# term_work.net
KiCad netlist of a schematic drawn in EasyEDA Pro
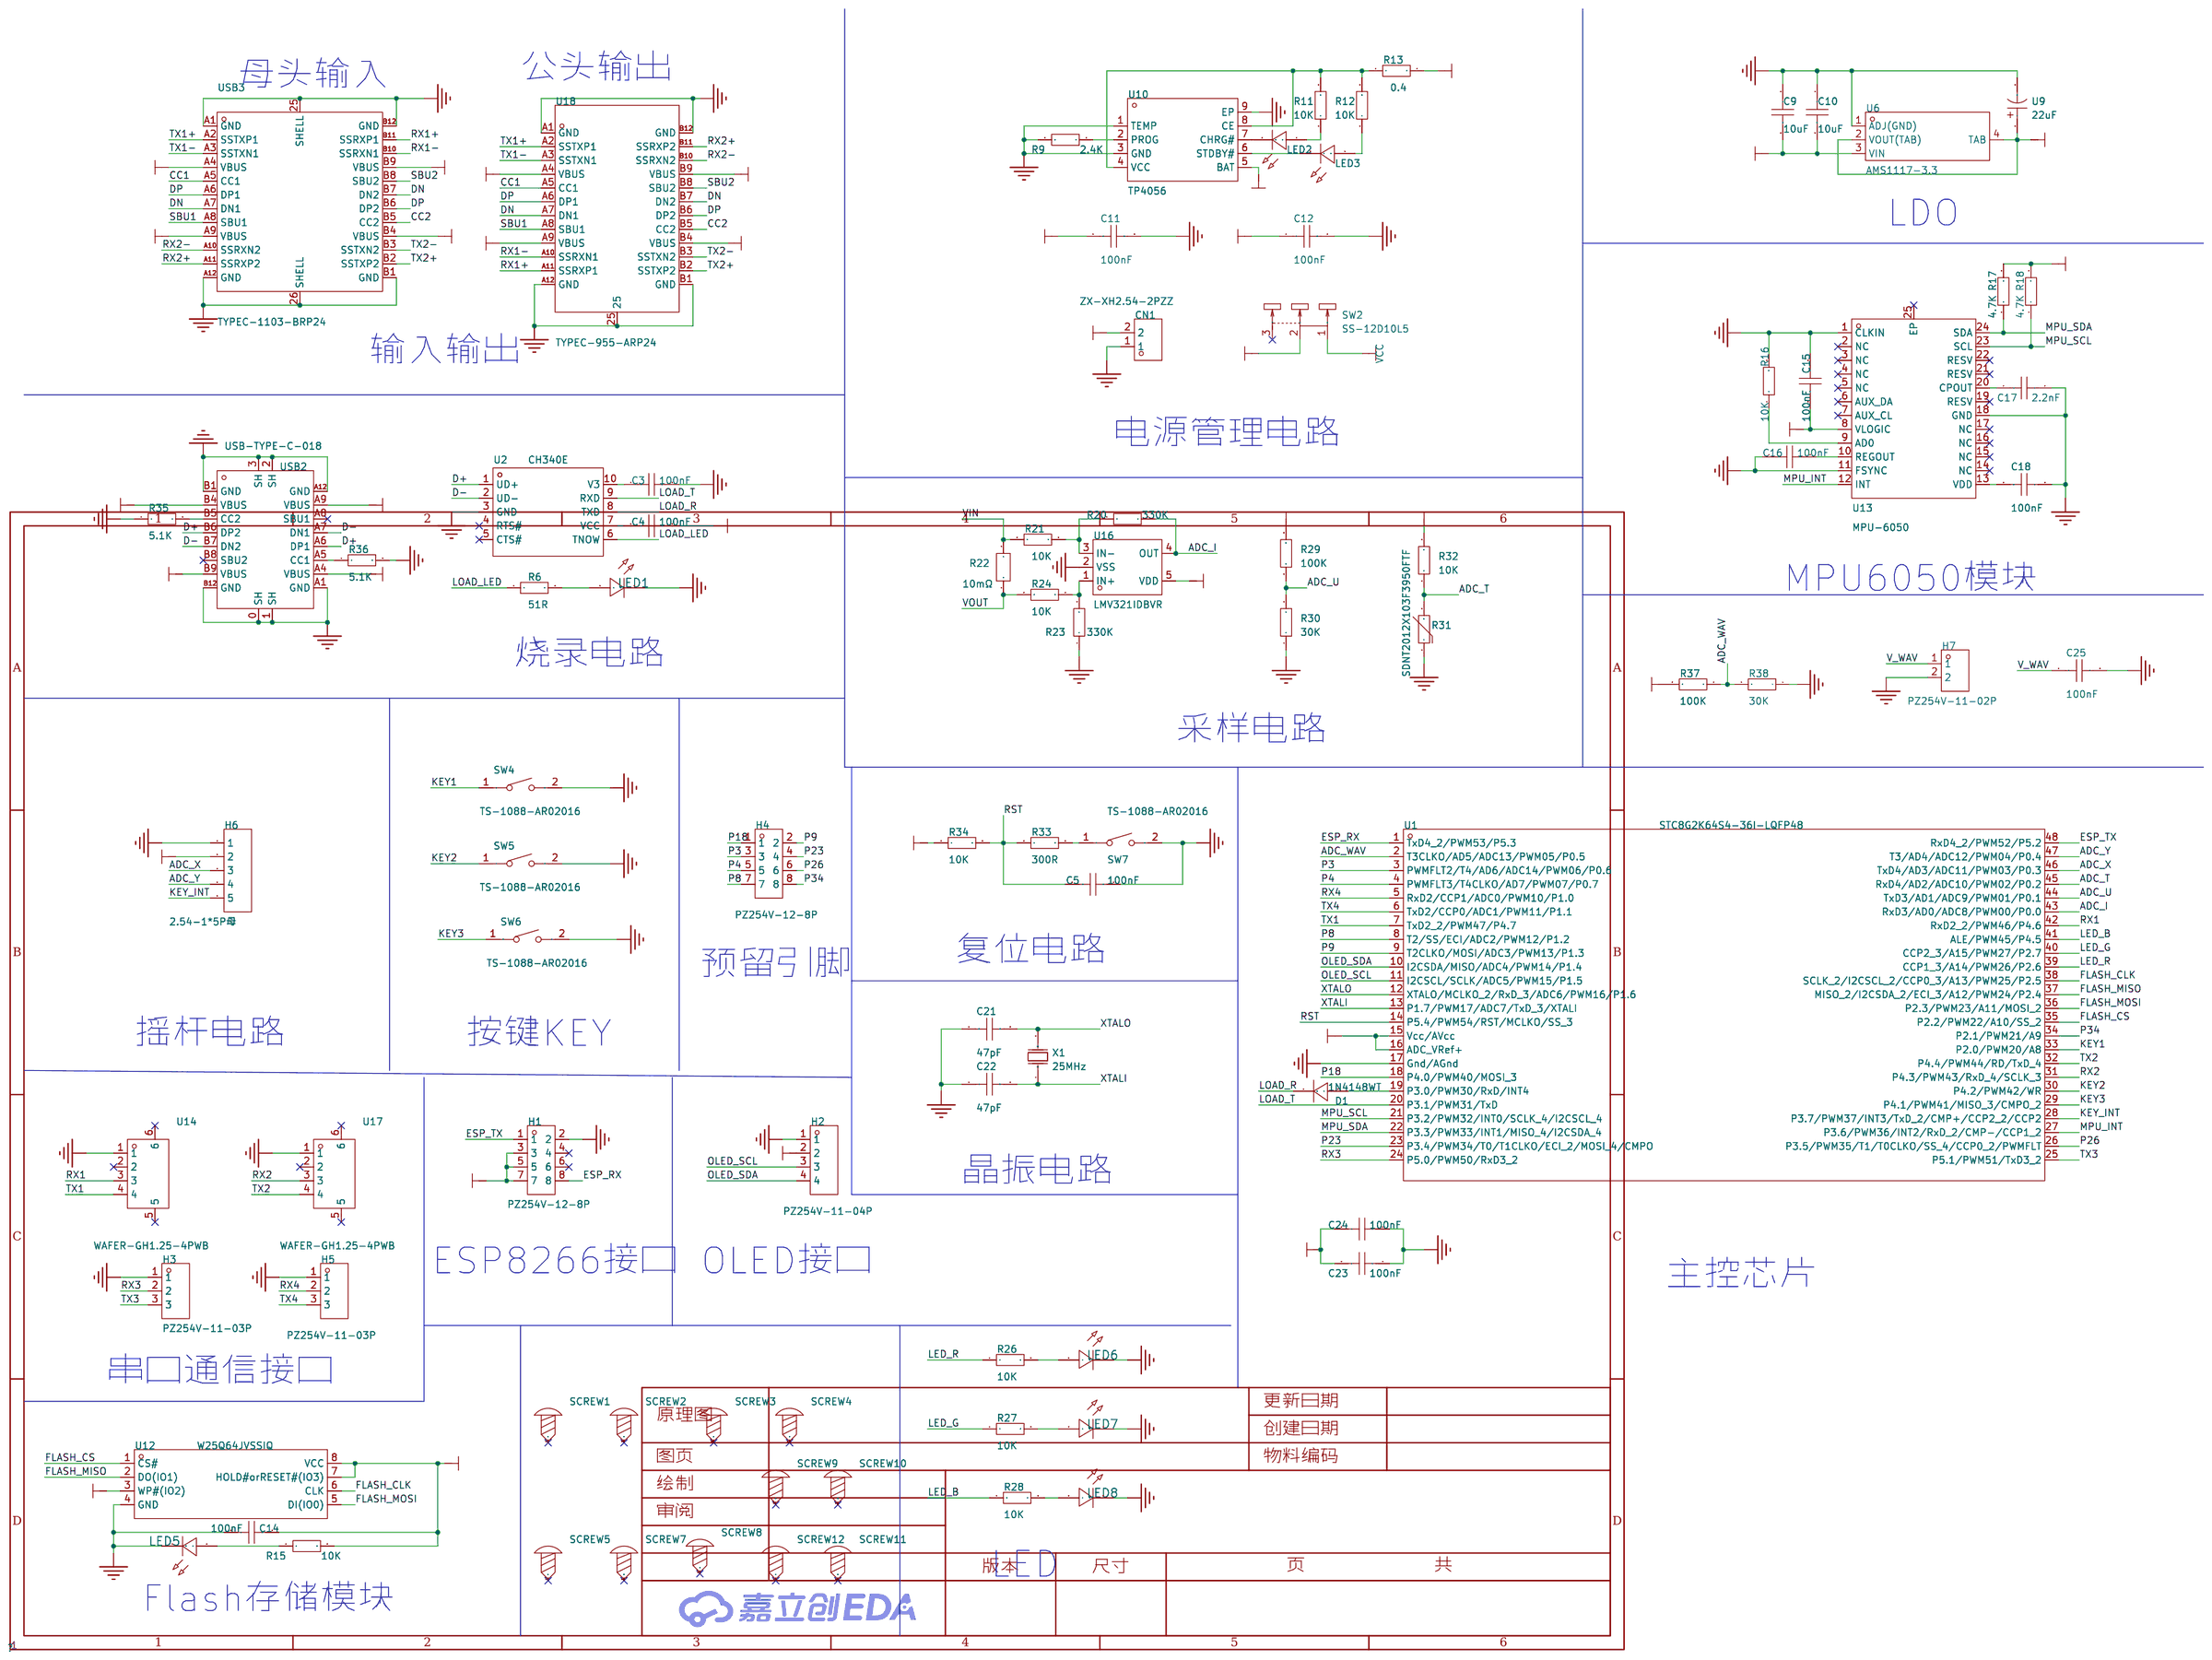
[diagram p0: schematic sheet]

(export (version "E")
  (design (tool "Eeschema 10.0.6"))
  (components
    (comp (ref "C3")
      (value "100nF")
      (footprint "easyedapro:C0603")
      (libsource (lib "easyedapro") (part "CapAcitance"))
    )
    (comp (ref "C4")
      (value "100nF")
      (footprint "easyedapro:C0603")
      (libsource (lib "easyedapro") (part "CapAcitance"))
    )
    (comp (ref "C5")
      (value "100nF")
      (footprint "easyedapro:C0603")
      (libsource (lib "easyedapro") (part "CapAcitance"))
    )
    (comp (ref "C9")
      (value "10uF")
      (footprint "easyedapro:C0603")
      (libsource (lib "easyedapro") (part "CapAcitance"))
    )
    (comp (ref "C10")
      (value "10uF")
      (footprint "easyedapro:C0603")
      (libsource (lib "easyedapro") (part "CapAcitance"))
    )
    (comp (ref "C11")
      (value "100nF")
      (footprint "easyedapro:C0603")
      (libsource (lib "easyedapro") (part "CapAcitance"))
    )
    (comp (ref "C12")
      (value "100nF")
      (footprint "easyedapro:C0603")
      (libsource (lib "easyedapro") (part "CapAcitance"))
    )
    (comp (ref "C14")
      (value "100nF")
      (footprint "easyedapro:C0603")
      (libsource (lib "easyedapro") (part "CapAcitance"))
    )
    (comp (ref "C15")
      (value "100nF")
      (footprint "easyedapro:C0603")
      (libsource (lib "easyedapro") (part "CapAcitance"))
    )
    (comp (ref "C16")
      (value "100nF")
      (footprint "easyedapro:C0603")
      (libsource (lib "easyedapro") (part "CapAcitance"))
    )
    (comp (ref "C17")
      (value "2.2nF")
      (footprint "easyedapro:C0603")
      (libsource (lib "easyedapro") (part "CapAcitance"))
    )
    (comp (ref "C18")
      (value "100nF")
      (footprint "easyedapro:C0603")
      (libsource (lib "easyedapro") (part "CapAcitance"))
    )
    (comp (ref "C21")
      (value "47pF")
      (footprint "easyedapro:C0603")
      (libsource (lib "easyedapro") (part "CapAcitance"))
    )
    (comp (ref "C22")
      (value "47pF")
      (footprint "easyedapro:C0603")
      (libsource (lib "easyedapro") (part "CapAcitance"))
    )
    (comp (ref "C23")
      (value "100nF")
      (footprint "easyedapro:C0603")
      (libsource (lib "easyedapro") (part "CapAcitance"))
    )
    (comp (ref "C24")
      (value "100nF")
      (footprint "easyedapro:C0603")
      (libsource (lib "easyedapro") (part "CapAcitance"))
    )
    (comp (ref "C25")
      (value "100nF")
      (footprint "easyedapro:C0603")
      (libsource (lib "easyedapro") (part "CapAcitance"))
    )
    (comp (ref "CN1")
      (value "ZX-XH2.54-2PZZ")
      (footprint "easyedapro:CONN-TH_2P-P2.50_HX25003-2A")
      (fields (field (name "Manufacturer") "Megastar(兆星)"))
      (libsource (lib "easyedapro") (part "ZX-XH2.54-2PZZ"))
    )
    (comp (ref "D1")
      (value "1N4148WT")
      (footprint "easyedapro:SOD-523_L1.2-W0.8-LS1.6-RD")
      (description "二极管配置:独立式;正向压降(Vf):1V@10mA;直流反向耐压(Vr):75V;平均整流电流(Io):300mA;功率:200mW;反向恢复时间(trr):4ns;")
      (fields (field (name "Manufacturer") "onsemi(安森美)"))
      (libsource (lib "easyedapro") (part "1N4148WT_C232841"))
    )
    (comp (ref "H1")
      (value "PZ254V-12-8P")
      (footprint "easyedapro:HDR-TH_8P-P2.54-V-M-R2-C4-S2.54")
      (fields (field (name "Manufacturer") "XFCN(兴飞)"))
      (libsource (lib "easyedapro") (part "PZ254V-12-8P"))
    )
    (comp (ref "H2")
      (value "PZ254V-11-04P")
      (footprint "easyedapro:HDR-TH_4P-P2.54-V-M")
      (fields (field (name "Manufacturer") "XFCN(兴飞)"))
      (libsource (lib "easyedapro") (part "PZ254V-11-04P_C2691448"))
    )
    (comp (ref "H3")
      (value "PZ254V-11-03P")
      (footprint "easyedapro:HDR-TH_3P-P2.54-V-M")
      (fields (field (name "Manufacturer") "XFCN(兴飞)"))
      (libsource (lib "easyedapro") (part "PZ254V-11-03P_C2937625"))
    )
    (comp (ref "H4")
      (value "PZ254V-12-8P")
      (footprint "easyedapro:HDR-TH_8P-P2.54-V-M-R2-C4-S2.54")
      (fields (field (name "Manufacturer") "XFCN(兴飞)"))
      (libsource (lib "easyedapro") (part "PZ254V-12-8P"))
    )
    (comp (ref "H5")
      (value "PZ254V-11-03P")
      (footprint "easyedapro:HDR-TH_3P-P2.54-V-M")
      (fields (field (name "Manufacturer") "XFCN(兴飞)"))
      (libsource (lib "easyedapro") (part "PZ254V-11-03P_C2937625"))
    )
    (comp (ref "H6")
      (value "2.54-1*5P母")
      (footprint "easyedapro:HDR-TH_5P-P2.54-V-F")
      (description "插孔结构:1x5P;间距:2.54mm;行距:-;安装类型:直插;排数:单排;总孔位数:5P;塑高:-;触头材质:-;触头镀层:-;")
      (fields (field (name "Manufacturer") "BOOMELE(博穆精密)"))
      (libsource (lib "easyedapro") (part "Header-Female-2.54_1x5"))
    )
    (comp (ref "H7")
      (value "PZ254V-11-02P")
      (footprint "easyedapro:HDR-TH_2P-P2.54-V-M")
      (fields (field (name "Manufacturer") "XFCN(兴飞)"))
      (libsource (lib "easyedapro") (part "PZ254V-11-02P"))
    )
    (comp (ref "LED1")
      (value "~")
      (footprint "easyedapro:LED_0603")
      (libsource (lib "easyedapro") (part "LED_R"))
    )
    (comp (ref "LED2")
      (value "~")
      (footprint "easyedapro:LED_TH-3mm")
      (libsource (lib "easyedapro") (part "LED_TH-R"))
    )
    (comp (ref "LED3")
      (value "~")
      (footprint "easyedapro:LED_TH-3mm")
      (libsource (lib "easyedapro") (part "LED_TH-R"))
    )
    (comp (ref "LED5")
      (value "~")
      (footprint "easyedapro:LED_0603")
      (libsource (lib "easyedapro") (part "LED_R"))
    )
    (comp (ref "LED6")
      (value "~")
      (footprint "easyedapro:LED_0603")
      (libsource (lib "easyedapro") (part "LED_R"))
    )
    (comp (ref "LED7")
      (value "~")
      (footprint "easyedapro:LED_0603")
      (libsource (lib "easyedapro") (part "LED_R"))
    )
    (comp (ref "LED8")
      (value "~")
      (footprint "easyedapro:LED_0603")
      (libsource (lib "easyedapro") (part "LED_R"))
    )
    (comp (ref "R6") (value "51R") (footprint "easyedapro:R0603") (libsource (lib "easyedapro") (part "电阻")))
    (comp (ref "R9") (value "2.4K") (footprint "easyedapro:R0603") (libsource (lib "easyedapro") (part "电阻")))
    (comp (ref "R11") (value "10K") (footprint "easyedapro:R0603") (libsource (lib "easyedapro") (part "电阻")))
    (comp (ref "R12") (value "10K") (footprint "easyedapro:R0603") (libsource (lib "easyedapro") (part "电阻")))
    (comp (ref "R13") (value "0.4") (footprint "easyedapro:R0603") (libsource (lib "easyedapro") (part "电阻")))
    (comp (ref "R15") (value "10K") (footprint "easyedapro:R0603") (libsource (lib "easyedapro") (part "电阻")))
    (comp (ref "R16") (value "10K") (footprint "easyedapro:R0603") (libsource (lib "easyedapro") (part "电阻")))
    (comp (ref "R17")
      (value "4.7K")
      (footprint "easyedapro:R0603")
      (libsource (lib "easyedapro") (part "电阻"))
    )
    (comp (ref "R18")
      (value "4.7K")
      (footprint "easyedapro:R0603")
      (libsource (lib "easyedapro") (part "电阻"))
    )
    (comp (ref "R20")
      (value "330K")
      (footprint "easyedapro:R0603")
      (libsource (lib "easyedapro") (part "电阻"))
    )
    (comp (ref "R21") (value "10K") (footprint "easyedapro:R0603") (libsource (lib "easyedapro") (part "电阻")))
    (comp (ref "R22")
      (value "10mΩ")
      (footprint "easyedapro:RES-SMD_L6.4-W3.2-1")
      (description "电阻类型:采样电阻;阻值:5mΩ;精度:±1%;功率:3W;安装方式:贴片;")
      (fields
        (field (name "Manufacturer Part") "HoJLR2512-3W-5mR-1%")
        (field (name "Manufacturer") "Milliohm(毫欧)")
      )
      (libsource (lib "easyedapro") (part "HOJLR2512-3W-5MR-1%"))
    )
    (comp (ref "R23")
      (value "330K")
      (footprint "easyedapro:R0603")
      (libsource (lib "easyedapro") (part "电阻"))
    )
    (comp (ref "R24") (value "10K") (footprint "easyedapro:R0603") (libsource (lib "easyedapro") (part "电阻")))
    (comp (ref "R26") (value "10K") (footprint "easyedapro:R0603") (libsource (lib "easyedapro") (part "电阻")))
    (comp (ref "R27") (value "10K") (footprint "easyedapro:R0603") (libsource (lib "easyedapro") (part "电阻")))
    (comp (ref "R28") (value "10K") (footprint "easyedapro:R0603") (libsource (lib "easyedapro") (part "电阻")))
    (comp (ref "R29")
      (value "100K")
      (footprint "easyedapro:R0603")
      (libsource (lib "easyedapro") (part "电阻"))
    )
    (comp (ref "R30") (value "30K") (footprint "easyedapro:R0603") (libsource (lib "easyedapro") (part "电阻")))
    (comp (ref "R31")
      (value "SDNT2012X103F3950FTF")
      (footprint "easyedapro:R0805")
      (description "阻值(25°C):10kΩ;B值(25°C/50°C):3950K;电阻精度:±1%;功率:200mW;B值精度:±1%;最大稳态电流(25°C):440uA;")
      (fields (field (name "Manufacturer") "Sunlord(顺络)"))
      (libsource (lib "easyedapro") (part "SDNT2012X103F3950FTF"))
    )
    (comp (ref "R32") (value "10K") (footprint "easyedapro:R0603") (libsource (lib "easyedapro") (part "电阻")))
    (comp (ref "R33")
      (value "300R")
      (footprint "easyedapro:R0603")
      (libsource (lib "easyedapro") (part "电阻"))
    )
    (comp (ref "R34") (value "10K") (footprint "easyedapro:R0603") (libsource (lib "easyedapro") (part "电阻")))
    (comp (ref "R35")
      (value "5.1K")
      (footprint "easyedapro:R0603")
      (libsource (lib "easyedapro") (part "电阻"))
    )
    (comp (ref "R36")
      (value "5.1K")
      (footprint "easyedapro:R0603")
      (libsource (lib "easyedapro") (part "电阻"))
    )
    (comp (ref "R37")
      (value "100K")
      (footprint "easyedapro:R0603")
      (libsource (lib "easyedapro") (part "电阻"))
    )
    (comp (ref "R38") (value "30K") (footprint "easyedapro:R0603") (libsource (lib "easyedapro") (part "电阻")))
    (comp (ref "SCREW1")
      (value "~")
      (footprint "easyedapro:M3螺丝")
      (libsource (lib "easyedapro") (part "螺丝孔"))
    )
    (comp (ref "SCREW2")
      (value "~")
      (footprint "easyedapro:M3螺丝")
      (libsource (lib "easyedapro") (part "螺丝孔"))
    )
    (comp (ref "SCREW3")
      (value "~")
      (footprint "easyedapro:M3螺丝")
      (libsource (lib "easyedapro") (part "螺丝孔"))
    )
    (comp (ref "SCREW4")
      (value "~")
      (footprint "easyedapro:M3螺丝")
      (libsource (lib "easyedapro") (part "螺丝孔"))
    )
    (comp (ref "SCREW5")
      (value "~")
      (footprint "easyedapro:M3螺丝")
      (libsource (lib "easyedapro") (part "螺丝孔"))
    )
    (comp (ref "SCREW7")
      (value "~")
      (footprint "easyedapro:M3螺丝")
      (libsource (lib "easyedapro") (part "螺丝孔"))
    )
    (comp (ref "SCREW8")
      (value "~")
      (footprint "easyedapro:M3螺丝")
      (libsource (lib "easyedapro") (part "螺丝孔"))
    )
    (comp (ref "SCREW9")
      (value "~")
      (footprint "easyedapro:M3螺丝")
      (libsource (lib "easyedapro") (part "螺丝孔"))
    )
    (comp (ref "SCREW10")
      (value "~")
      (footprint "easyedapro:M3螺丝")
      (libsource (lib "easyedapro") (part "螺丝孔"))
    )
    (comp (ref "SCREW11")
      (value "~")
      (footprint "easyedapro:M3螺丝")
      (libsource (lib "easyedapro") (part "螺丝孔"))
    )
    (comp (ref "SCREW12")
      (value "~")
      (footprint "easyedapro:M3螺丝")
      (libsource (lib "easyedapro") (part "螺丝孔"))
    )
    (comp (ref "SW2")
      (value "SS-12D10L5")
      (footprint "easyedapro:SW-TH_SS-12D10L5")
      (description "电路结构:单刀双掷;安装方式:直插;开关颜色:黑色;额定电流(DC):3A;额定电压(DC):125V;额定电流(AC):3A;额定电压(AC):125V;机械寿命:1万次;")
      (fields (field (name "Manufacturer") "XKB Connectivity(中国星坤)"))
      (libsource (lib "easyedapro") (part "SS-12D10L5"))
    )
    (comp (ref "SW4")
      (value "TS-1088-AR02016")
      (footprint "easyedapro:SW-SMD_L3.9-W3.0-P4.45")
      (fields (field (name "Manufacturer") "XUNPU(讯普)"))
      (libsource (lib "easyedapro") (part "TS-1088-AR02016"))
    )
    (comp (ref "SW5")
      (value "TS-1088-AR02016")
      (footprint "easyedapro:SW-SMD_L3.9-W3.0-P4.45")
      (fields (field (name "Manufacturer") "XUNPU(讯普)"))
      (libsource (lib "easyedapro") (part "TS-1088-AR02016"))
    )
    (comp (ref "SW6")
      (value "TS-1088-AR02016")
      (footprint "easyedapro:SW-SMD_L3.9-W3.0-P4.45")
      (fields (field (name "Manufacturer") "XUNPU(讯普)"))
      (libsource (lib "easyedapro") (part "TS-1088-AR02016"))
    )
    (comp (ref "SW7")
      (value "TS-1088-AR02016")
      (footprint "easyedapro:SW-SMD_L3.9-W3.0-P4.45")
      (fields (field (name "Manufacturer") "XUNPU(讯普)"))
      (libsource (lib "easyedapro") (part "TS-1088-AR02016"))
    )
    (comp (ref "U1")
      (value "STC8G2K64S4-36I-LQFP48")
      (footprint "easyedapro:LQFP-48_L7.0-W7.0-P0.50-LS9.0-BL")
      (description "CPU内核:51系列;程序存储容量:64KB;RAM总容量:2.25KB;GPIO端口数量:45;工作电压范围:1.9V~5.5V;CPU最大主频:-;程序存储器类型:FLASH;")
      (fields (field (name "Manufacturer") "STC(宏晶)"))
      (libsource (lib "easyedapro") (part "STC8G2K64S4-36I-LQFP48"))
    )
    (comp (ref "U2")
      (value "CH340E")
      (footprint "easyedapro:MSOP-10_L3.0-W3.0-P0.50-LS5.0-BL")
      (description "应用功能:收发器;接口协议:USB 2.0;数据速率:2Mbps;")
      (fields (field (name "Manufacturer") "WCH(南京沁恒)"))
      (libsource (lib "easyedapro") (part "CH340E"))
    )
    (comp (ref "U6")
      (value "AMS1117-3.3")
      (footprint "easyedapro:SOT-223-4_L6.5-W3.5-P2.30-LS7.0-BR")
      (description "输出类型:固定;最大输入电压:18V;输出电压:3.3V;输出电流:1A;电源纹波抑制比(PSRR):60dB@(120Hz);输出极性:正极;")
      (fields (field (name "Manufacturer") "UMW(友台半导体)"))
      (libsource (lib "easyedapro") (part "AMS1117-3.3_C347222"))
    )
    (comp (ref "U9")
      (value "22uF")
      (footprint "easyedapro:CAP-SMD_L2.0-W1.3-FD")
      (description "容值:22uF;精度:±20%;额定电压:6.3V;等效串联电阻:5.9Ω@100kHz;")
      (fields (field (name "Manufacturer Part") "TMCP0J226MTRF") (field (name "Manufacturer") "VISHAY(威世)"))
      (libsource (lib "easyedapro") (part "TMCP0J226MTRF"))
    )
    (comp (ref "U10")
      (value "TP4056")
      (footprint "easyedapro:ESOP-8_L4.9-W3.9-P1.27-LS6.0-BL-EP")
      (fields (field (name "Manufacturer") "UMW(友台半导体)"))
      (libsource (lib "easyedapro") (part "TP4056_C725790"))
    )
    (comp (ref "U12")
      (value "W25Q64JVSSIQ")
      (footprint "easyedapro:SOIC-8_L5.3-W5.3-P1.27-LS8.0-BL")
      (fields (field (name "Manufacturer") "WINBOND(华邦)"))
      (libsource (lib "easyedapro") (part "W25Q64JVSSIQ_C179171"))
    )
    (comp (ref "U13")
      (value "MPU-6050")
      (footprint "easyedapro:QFN-24_L4.0-W4.0-P0.50-BL-EP2.7")
      (description "传感器类型:加速度计陀螺仪;")
      (fields (field (name "Manufacturer") "TDK InvenSense(应美盛)"))
      (libsource (lib "easyedapro") (part "MPU-6050_C24112"))
    )
    (comp (ref "U14")
      (value "WAFER-GH1.25-4PWB")
      (footprint "easyedapro:CONN-SMD_4P-P1.25_XUNPU_WAFER-GH1.25-4PWB")
      (description "插针结构:1x4P;间距:1.25mm;安装方式:卧贴;参考系列:GH;总PIN数:4P;排数:1;每排PIN数:4;额定电流:1A;工作温度范围:-25°C~+85°C;")
      (fields (field (name "Manufacturer") "XUNPU(讯普)"))
      (libsource (lib "easyedapro") (part "WAFER-GH1.25-4PWB"))
    )
    (comp (ref "U16")
      (value "LMV321IDBVR")
      (footprint "easyedapro:SOT-23-5_L2.9-W1.6-P0.95-LS2.8-BR")
      (description "低功耗运放")
      (fields (field (name "Manufacturer") "UMW(友台半导体)"))
      (libsource (lib "easyedapro") (part "LMV321IDBVR_C3014306"))
    )
    (comp (ref "U17")
      (value "WAFER-GH1.25-4PWB")
      (footprint "easyedapro:CONN-SMD_4P-P1.25_XUNPU_WAFER-GH1.25-4PWB")
      (description "插针结构:1x4P;间距:1.25mm;安装方式:卧贴;参考系列:GH;总PIN数:4P;排数:1;每排PIN数:4;额定电流:1A;工作温度范围:-25°C~+85°C;")
      (fields (field (name "Manufacturer") "XUNPU(讯普)"))
      (libsource (lib "easyedapro") (part "WAFER-GH1.25-4PWB"))
    )
    (comp (ref "U18")
      (value "TYPEC-955-ARP24")
      (footprint "easyedapro:TYPE-C-SMD_TYPEC-955-ARP24")
      (fields (field (name "Manufacturer") "XUNPU(讯普)"))
      (libsource (lib "easyedapro") (part "TYPEC-955-ARP24"))
    )
    (comp (ref "USB2")
      (value "USB-TYPE-C-018")
      (footprint "easyedapro:USB-C_SMD-TYPE-C-31-M-12")
      (description "连接器类型:Type-C;标准:-;公母:母;安装方式:卧贴;触点数量:16P;端口数量:1;额定电流 - 电源:3A;工作温度范围:-25°C~+85°C;")
      (fields (field (name "Manufacturer") "DEALON(德艺隆)"))
      (libsource (lib "easyedapro") (part "USB-TYPE-C-018"))
    )
    (comp (ref "USB3")
      (value "TYPEC-1103-BRP24")
      (footprint "easyedapro:USB-C-SMD_TYPEC-1103-BRP24")
      (fields (field (name "Manufacturer") "XUNPU(讯普)"))
      (libsource (lib "easyedapro") (part "TYPEC-1103-BRP24"))
    )
    (comp (ref "X1")
      (value "25MHz")
      (footprint "easyedapro:CRYSTAL-SMD_2P-L5.0-W3.2")
      (description "晶振类型:贴片晶振;频率:25MHz;常温频差:±10ppm;外接负载电容:20pF;频率稳定度(全温):±20ppm;")
      (fields
        (field (name "Manufacturer Part") "XG1EL89CSI-111YLC-25M")
        (field (name "Manufacturer") "YXC(扬兴晶振)")
      )
      (libsource (lib "easyedapro") (part "XG1EL89CSI-111YLC-25M"))
    )
  )
  (nets
    (net (code "1") (name "/ADC_I") (class "Default")
      (node (ref "R20") (pin "1") (pinfunction "1_1") (pintype "input"))
      (node (ref "U1") (pin "43") (pinfunction "RxD3/AD0/ADC8/PWM00/P0.0_43") (pintype "unspecified"))
      (node (ref "U16") (pin "4") (pinfunction "OUT_4") (pintype "unspecified"))
    )
    (net (code "2") (name "/ADC_T") (class "Default")
      (node (ref "R31") (pin "2") (pinfunction "2_2") (pintype "input"))
      (node (ref "R32") (pin "1") (pinfunction "1_1") (pintype "input"))
      (node (ref "U1") (pin "45") (pinfunction "RxD4/AD2/ADC10/PWM02/P0.2_45") (pintype "unspecified"))
    )
    (net (code "3") (name "/ADC_U") (class "Default")
      (node (ref "R29") (pin "1") (pinfunction "1_1") (pintype "input"))
      (node (ref "R30") (pin "2") (pinfunction "2_2") (pintype "input"))
      (node (ref "U1") (pin "44") (pinfunction "TxD3/AD1/ADC9/PWM01/P0.1_44") (pintype "unspecified"))
    )
    (net (code "4") (name "/ADC_WAV") (class "Default")
      (node (ref "R37") (pin "1") (pinfunction "1_1") (pintype "input"))
      (node (ref "R38") (pin "2") (pinfunction "2_2") (pintype "input"))
      (node (ref "U1") (pin "2") (pinfunction "T3CLKO/AD5/ADC13/PWM05/P0.5_2") (pintype "unspecified"))
    )
    (net (code "5") (name "/ADC_X") (class "Default")
      (node (ref "H6") (pin "3") (pinfunction "3_3") (pintype "input"))
      (node (ref "U1") (pin "46") (pinfunction "TxD4/AD3/ADC11/PWM03/P0.3_46") (pintype "unspecified"))
    )
    (net (code "6") (name "/ADC_Y") (class "Default")
      (node (ref "H6") (pin "4") (pinfunction "4_4") (pintype "input"))
      (node (ref "U1") (pin "47") (pinfunction "T3/AD4/ADC12/PWM04/P0.4_47") (pintype "unspecified"))
    )
    (net (code "7") (name "/CC1") (class "Default")
      (node (ref "U18") (pin "A5") (pinfunction "CC1_A5") (pintype "unspecified"))
      (node (ref "USB3") (pin "A5") (pinfunction "CC1_A5") (pintype "unspecified"))
    )
    (net (code "8") (name "/CC2") (class "Default")
      (node (ref "U18") (pin "B5") (pinfunction "CC2_B5") (pintype "unspecified"))
      (node (ref "USB3") (pin "B5") (pinfunction "CC2_B5") (pintype "unspecified"))
    )
    (net (code "9") (name "/D+") (class "Default")
      (node (ref "U2") (pin "1") (pinfunction "UD+_1") (pintype "unspecified"))
      (node (ref "USB2") (pin "A6") (pinfunction "DP1_A6") (pintype "unspecified"))
      (node (ref "USB2") (pin "B6") (pinfunction "DP2_B6") (pintype "unspecified"))
    )
    (net (code "10") (name "/D-") (class "Default")
      (node (ref "U2") (pin "2") (pinfunction "UD-_2") (pintype "unspecified"))
      (node (ref "USB2") (pin "A7") (pinfunction "DN1_A7") (pintype "unspecified"))
      (node (ref "USB2") (pin "B7") (pinfunction "DN2_B7") (pintype "unspecified"))
    )
    (net (code "11") (name "/DN") (class "Default")
      (node (ref "U18") (pin "A7") (pinfunction "DN1_A7") (pintype "unspecified"))
      (node (ref "U18") (pin "B7") (pinfunction "DN2_B7") (pintype "unspecified"))
      (node (ref "USB3") (pin "A7") (pinfunction "DN1_A7") (pintype "unspecified"))
      (node (ref "USB3") (pin "B7") (pinfunction "DN2_B7") (pintype "unspecified"))
    )
    (net (code "12") (name "/DP") (class "Default")
      (node (ref "U18") (pin "A6") (pinfunction "DP1_A6") (pintype "unspecified"))
      (node (ref "U18") (pin "B6") (pinfunction "DP2_B6") (pintype "unspecified"))
      (node (ref "USB3") (pin "A6") (pinfunction "DP1_A6") (pintype "unspecified"))
      (node (ref "USB3") (pin "B6") (pinfunction "DP2_B6") (pintype "unspecified"))
    )
    (net (code "13") (name "/ESP_RX") (class "Default")
      (node (ref "H1") (pin "8") (pinfunction "8_8") (pintype "unspecified"))
      (node (ref "U1") (pin "1") (pinfunction "TxD4_2/PWM53/P5.3_1") (pintype "unspecified"))
    )
    (net (code "14") (name "/ESP_TX") (class "Default")
      (node (ref "H1") (pin "1") (pinfunction "1_1") (pintype "unspecified"))
      (node (ref "U1") (pin "48") (pinfunction "RxD4_2/PWM52/P5.2_48") (pintype "unspecified"))
    )
    (net (code "15") (name "/FLASH_CLK") (class "Default")
      (node (ref "U1") (pin "38") (pinfunction "SCLK_2/I2CSCL_2/CCP0_3/A13/PWM25/P2.5_38") (pintype "unspecified"))
      (node (ref "U12") (pin "6") (pinfunction "CLK_6") (pintype "unspecified"))
    )
    (net (code "16") (name "/FLASH_CS") (class "Default")
      (node (ref "U1") (pin "35") (pinfunction "P2.2/PWM22/A10/SS_2_35") (pintype "unspecified"))
      (node (ref "U12") (pin "1") (pinfunction "CS#_1") (pintype "unspecified"))
    )
    (net (code "17") (name "/FLASH_MISO") (class "Default")
      (node (ref "U1") (pin "37") (pinfunction "MISO_2/I2CSDA_2/ECI_3/A12/PWM24/P2.4_37") (pintype "unspecified"))
      (node (ref "U12") (pin "2") (pinfunction "DO(IO1)_2") (pintype "unspecified"))
    )
    (net (code "18") (name "/FLASH_MOSI") (class "Default")
      (node (ref "U1") (pin "36") (pinfunction "P2.3/PWM23/A11/MOSI_2_36") (pintype "unspecified"))
      (node (ref "U12") (pin "5") (pinfunction "DI(IO0)_5") (pintype "unspecified"))
    )
    (net (code "19") (name "/KEY1") (class "Default")
      (node (ref "SW4") (pin "1") (pinfunction "1_1") (pintype "unspecified"))
      (node (ref "U1") (pin "33") (pinfunction "P2.0/PWM20/A8_33") (pintype "unspecified"))
    )
    (net (code "20") (name "/KEY2") (class "Default")
      (node (ref "SW5") (pin "1") (pinfunction "1_1") (pintype "unspecified"))
      (node (ref "U1") (pin "30") (pinfunction "P4.2/PWM42/WR_30") (pintype "unspecified"))
    )
    (net (code "21") (name "/KEY3") (class "Default")
      (node (ref "SW6") (pin "1") (pinfunction "1_1") (pintype "unspecified"))
      (node (ref "U1") (pin "29") (pinfunction "P4.1/PWM41/MISO_3/CMPO_2_29") (pintype "unspecified"))
    )
    (net (code "22") (name "/KEY_INT") (class "Default")
      (node (ref "H6") (pin "5") (pinfunction "5_5") (pintype "input"))
      (node (ref "U1") (pin "28") (pinfunction "P3.7/PWM37/INT3/TxD_2/CMP+/CCP2_2/CCP2_28") (pintype "unspecified"))
    )
    (net (code "23") (name "/LED_B") (class "Default")
      (node (ref "R28") (pin "1") (pinfunction "1_1") (pintype "input"))
      (node (ref "U1") (pin "41") (pinfunction "ALE/PWM45/P4.5_41") (pintype "unspecified"))
    )
    (net (code "24") (name "/LED_G") (class "Default")
      (node (ref "R27") (pin "1") (pinfunction "1_1") (pintype "input"))
      (node (ref "U1") (pin "40") (pinfunction "CCP2_3/A15/PWM27/P2.7_40") (pintype "unspecified"))
    )
    (net (code "25") (name "/LED_R") (class "Default")
      (node (ref "R26") (pin "1") (pinfunction "1_1") (pintype "input"))
      (node (ref "U1") (pin "39") (pinfunction "CCP1_3/A14/PWM26/P2.6_39") (pintype "unspecified"))
    )
    (net (code "26") (name "/LOAD_LED") (class "Default")
      (node (ref "R6") (pin "1") (pinfunction "1_1") (pintype "input"))
      (node (ref "U2") (pin "6") (pinfunction "TNOW_6") (pintype "unspecified"))
    )
    (net (code "27") (name "/LOAD_R") (class "Default")
      (node (ref "D1") (pin "1") (pinfunction "C_1") (pintype "unspecified"))
      (node (ref "U2") (pin "8") (pinfunction "TXD_8") (pintype "unspecified"))
    )
    (net (code "28") (name "/LOAD_T") (class "Default")
      (node (ref "U1") (pin "20") (pinfunction "P3.1/PWM31/TxD_20") (pintype "unspecified"))
      (node (ref "U2") (pin "9") (pinfunction "RXD_9") (pintype "unspecified"))
    )
    (net (code "29") (name "/MPU_INT") (class "Default")
      (node (ref "U1") (pin "27") (pinfunction "P3.6/PWM36/INT2/RxD_2/CMP-/CCP1_2_27") (pintype "unspecified"))
      (node (ref "U13") (pin "12") (pinfunction "INT_12") (pintype "unspecified"))
    )
    (net (code "30") (name "/MPU_SCL") (class "Default")
      (node (ref "R18") (pin "1") (pinfunction "1_1") (pintype "input"))
      (node (ref "U1") (pin "21") (pinfunction "P3.2/PWM32/INT0/SCLK_4/I2CSCL_4_21") (pintype "unspecified"))
      (node (ref "U13") (pin "23") (pinfunction "SCL_23") (pintype "unspecified"))
    )
    (net (code "31") (name "/MPU_SDA") (class "Default")
      (node (ref "R17") (pin "1") (pinfunction "1_1") (pintype "input"))
      (node (ref "U1") (pin "22") (pinfunction "P3.3/PWM33/INT1/MISO_4/I2CSDA_4_22") (pintype "unspecified"))
      (node (ref "U13") (pin "24") (pinfunction "SDA_24") (pintype "unspecified"))
    )
    (net (code "32") (name "/OLED_SCL") (class "Default")
      (node (ref "H2") (pin "3") (pinfunction "3_3") (pintype "unspecified"))
      (node (ref "U1") (pin "11") (pinfunction "I2CSCL/SCLK/ADC5/PWM15/P1.5_11") (pintype "unspecified"))
    )
    (net (code "33") (name "/OLED_SDA") (class "Default")
      (node (ref "H2") (pin "4") (pinfunction "4_4") (pintype "unspecified"))
      (node (ref "U1") (pin "10") (pinfunction "I2CSDA/MISO/ADC4/PWM14/P1.4_10") (pintype "unspecified"))
    )
    (net (code "34") (name "/P3") (class "Default")
      (node (ref "H4") (pin "3") (pinfunction "3_3") (pintype "unspecified"))
      (node (ref "U1") (pin "3") (pinfunction "PWMFLT2/T4/AD6/ADC14/PWM06/P0.6_3") (pintype "unspecified"))
    )
    (net (code "35") (name "/P4") (class "Default")
      (node (ref "H4") (pin "5") (pinfunction "5_5") (pintype "unspecified"))
      (node (ref "U1") (pin "4") (pinfunction "PWMFLT3/T4CLKO/AD7/PWM07/P0.7_4") (pintype "unspecified"))
    )
    (net (code "36") (name "/P8") (class "Default")
      (node (ref "H4") (pin "7") (pinfunction "7_7") (pintype "unspecified"))
      (node (ref "U1") (pin "8") (pinfunction "T2/SS/ECI/ADC2/PWM12/P1.2_8") (pintype "unspecified"))
    )
    (net (code "37") (name "/P9") (class "Default")
      (node (ref "H4") (pin "2") (pinfunction "2_2") (pintype "unspecified"))
      (node (ref "U1") (pin "9") (pinfunction "T2CLKO/MOSI/ADC3/PWM13/P1.3_9") (pintype "unspecified"))
    )
    (net (code "38") (name "/P18") (class "Default")
      (node (ref "H4") (pin "1") (pinfunction "1_1") (pintype "unspecified"))
      (node (ref "U1") (pin "18") (pinfunction "P4.0/PWM40/MOSI_3_18") (pintype "unspecified"))
    )
    (net (code "39") (name "/P23") (class "Default")
      (node (ref "H4") (pin "4") (pinfunction "4_4") (pintype "unspecified"))
      (node (ref "U1") (pin "23") (pinfunction "P3.4/PWM34/T0/T1CLKO/ECI_2/MOSI_4/CMPO_23") (pintype "unspecified"))
    )
    (net (code "40") (name "/P26") (class "Default")
      (node (ref "H4") (pin "6") (pinfunction "6_6") (pintype "unspecified"))
      (node (ref "U1") (pin "26") (pinfunction "P3.5/PWM35/T1/T0CLKO/SS_4/CCP0_2/PWMFLT_26") (pintype "unspecified"))
    )
    (net (code "41") (name "/P34") (class "Default")
      (node (ref "H4") (pin "8") (pinfunction "8_8") (pintype "unspecified"))
      (node (ref "U1") (pin "34") (pinfunction "P2.1/PWM21/A9_34") (pintype "unspecified"))
    )
    (net (code "42") (name "/RST") (class "Default")
      (node (ref "C5") (pin "2") (pinfunction "2_2") (pintype "input"))
      (node (ref "R33") (pin "1") (pinfunction "1_1") (pintype "input"))
      (node (ref "R34") (pin "2") (pinfunction "2_2") (pintype "input"))
      (node (ref "U1") (pin "14") (pinfunction "P5.4/PWM54/RST/MCLKO/SS_3_14") (pintype "unspecified"))
    )
    (net (code "43") (name "/RX1") (class "Default")
      (node (ref "U1") (pin "42") (pinfunction "RxD2_2/PWM46/P4.6_42") (pintype "unspecified"))
      (node (ref "U14") (pin "3") (pinfunction "3_3") (pintype "unspecified"))
    )
    (net (code "44") (name "/RX1+") (class "Default")
      (node (ref "U18") (pin "A11") (pinfunction "SSRXP1_A11") (pintype "unspecified"))
      (node (ref "USB3") (pin "B11") (pinfunction "SSRXP1_B11") (pintype "unspecified"))
    )
    (net (code "45") (name "/RX1-") (class "Default")
      (node (ref "U18") (pin "A10") (pinfunction "SSRXN1_A10") (pintype "unspecified"))
      (node (ref "USB3") (pin "B10") (pinfunction "SSRXN1_B10") (pintype "unspecified"))
    )
    (net (code "46") (name "/RX2") (class "Default")
      (node (ref "U1") (pin "31") (pinfunction "P4.3/PWM43/RxD_4/SCLK_3_31") (pintype "unspecified"))
      (node (ref "U17") (pin "3") (pinfunction "3_3") (pintype "unspecified"))
    )
    (net (code "47") (name "/RX2+") (class "Default")
      (node (ref "U18") (pin "B11") (pinfunction "SSRXP2_B11") (pintype "unspecified"))
      (node (ref "USB3") (pin "A11") (pinfunction "SSRXP2_A11") (pintype "unspecified"))
    )
    (net (code "48") (name "/RX2-") (class "Default")
      (node (ref "U18") (pin "B10") (pinfunction "SSRXN2_B10") (pintype "unspecified"))
      (node (ref "USB3") (pin "A10") (pinfunction "SSRXN2_A10") (pintype "unspecified"))
    )
    (net (code "49") (name "/RX3") (class "Default")
      (node (ref "H3") (pin "2") (pinfunction "2_2") (pintype "unspecified"))
      (node (ref "U1") (pin "24") (pinfunction "P5.0/PWM50/RxD3_2_24") (pintype "unspecified"))
    )
    (net (code "50") (name "/RX4") (class "Default")
      (node (ref "H5") (pin "2") (pinfunction "2_2") (pintype "unspecified"))
      (node (ref "U1") (pin "5") (pinfunction "RxD2/CCP1/ADC0/PWM10/P1.0_5") (pintype "unspecified"))
    )
    (net (code "51") (name "/SBU1") (class "Default")
      (node (ref "U18") (pin "A8") (pinfunction "SBU1_A8") (pintype "unspecified"))
      (node (ref "USB3") (pin "A8") (pinfunction "SBU1_A8") (pintype "unspecified"))
    )
    (net (code "52") (name "/SBU2") (class "Default")
      (node (ref "U18") (pin "B8") (pinfunction "SBU2_B8") (pintype "unspecified"))
      (node (ref "USB3") (pin "B8") (pinfunction "SBU2_B8") (pintype "unspecified"))
    )
    (net (code "53") (name "/TX1") (class "Default")
      (node (ref "U1") (pin "7") (pinfunction "TxD2_2/PWM47/P4.7_7") (pintype "unspecified"))
      (node (ref "U14") (pin "4") (pinfunction "4_4") (pintype "unspecified"))
    )
    (net (code "54") (name "/TX1+") (class "Default")
      (node (ref "U18") (pin "A2") (pinfunction "SSTXP1_A2") (pintype "unspecified"))
      (node (ref "USB3") (pin "A2") (pinfunction "SSTXP1_A2") (pintype "unspecified"))
    )
    (net (code "55") (name "/TX1-") (class "Default")
      (node (ref "U18") (pin "A3") (pinfunction "SSTXN1_A3") (pintype "unspecified"))
      (node (ref "USB3") (pin "A3") (pinfunction "SSTXN1_A3") (pintype "unspecified"))
    )
    (net (code "56") (name "/TX2") (class "Default")
      (node (ref "U1") (pin "32") (pinfunction "P4.4/PWM44/RD/TxD_4_32") (pintype "unspecified"))
      (node (ref "U17") (pin "4") (pinfunction "4_4") (pintype "unspecified"))
    )
    (net (code "57") (name "/TX2+") (class "Default")
      (node (ref "U18") (pin "B2") (pinfunction "SSTXP2_B2") (pintype "unspecified"))
      (node (ref "USB3") (pin "B2") (pinfunction "SSTXP2_B2") (pintype "unspecified"))
    )
    (net (code "58") (name "/TX2-") (class "Default")
      (node (ref "U18") (pin "B3") (pinfunction "SSTXN2_B3") (pintype "unspecified"))
      (node (ref "USB3") (pin "B3") (pinfunction "SSTXN2_B3") (pintype "unspecified"))
    )
    (net (code "59") (name "/TX3") (class "Default")
      (node (ref "H3") (pin "3") (pinfunction "3_3") (pintype "unspecified"))
      (node (ref "U1") (pin "25") (pinfunction "P5.1/PWM51/TxD3_2_25") (pintype "unspecified"))
    )
    (net (code "60") (name "/TX4") (class "Default")
      (node (ref "H5") (pin "3") (pinfunction "3_3") (pintype "unspecified"))
      (node (ref "U1") (pin "6") (pinfunction "TxD2/CCP0/ADC1/PWM11/P1.1_6") (pintype "unspecified"))
    )
    (net (code "61") (name "/XTALI") (class "Default")
      (node (ref "C22") (pin "2") (pinfunction "2_2") (pintype "input"))
      (node (ref "U1") (pin "13") (pinfunction "P1.7/PWM17/ADC7/TxD_3/XTALI_13") (pintype "unspecified"))
      (node (ref "X1") (pin "1") (pinfunction "OSC1_1") (pintype "input"))
    )
    (net (code "62") (name "/XTALO") (class "Default")
      (node (ref "C21") (pin "2") (pinfunction "2_2") (pintype "input"))
      (node (ref "U1") (pin "12") (pinfunction "XTALO/MCLKO_2/RxD_3/ADC6/PWM16/P1.6_12") (pintype "unspecified"))
      (node (ref "X1") (pin "2") (pinfunction "OSC2_2") (pintype "input"))
    )
    (net (code "63") (name "3V3") (class "Default")
      (node (ref "C14") (pin "2") (pinfunction "2_2") (pintype "input"))
      (node (ref "C15") (pin "1") (pinfunction "1_1") (pintype "input"))
      (node (ref "C23") (pin "2") (pinfunction "2_2") (pintype "input"))
      (node (ref "C24") (pin "2") (pinfunction "2_2") (pintype "input"))
      (node (ref "H1") (pin "3") (pinfunction "3_3") (pintype "unspecified"))
      (node (ref "H1") (pin "5") (pinfunction "5_5") (pintype "unspecified"))
      (node (ref "H1") (pin "7") (pinfunction "7_7") (pintype "unspecified"))
      (node (ref "H2") (pin "2") (pinfunction "2_2") (pintype "unspecified"))
      (node (ref "H6") (pin "2") (pinfunction "2_2") (pintype "input"))
      (node (ref "R15") (pin "2") (pinfunction "2_2") (pintype "input"))
      (node (ref "R17") (pin "2") (pinfunction "2_2") (pintype "input"))
      (node (ref "R18") (pin "2") (pinfunction "2_2") (pintype "input"))
      (node (ref "R32") (pin "2") (pinfunction "2_2") (pintype "input"))
      (node (ref "R34") (pin "1") (pinfunction "1_1") (pintype "input"))
      (node (ref "U1") (pin "15") (pinfunction "Vcc/AVcc_15") (pintype "unspecified"))
      (node (ref "U1") (pin "16") (pinfunction "ADC_VRef+_16") (pintype "unspecified"))
      (node (ref "U12") (pin "3") (pinfunction "WP#(IO2)_3") (pintype "unspecified"))
      (node (ref "U12") (pin "7") (pinfunction "HOLD#orRESET#(IO3)_7") (pintype "unspecified"))
      (node (ref "U12") (pin "8") (pinfunction "VCC_8") (pintype "unspecified"))
      (node (ref "U13") (pin "8") (pinfunction "VLOGIC_8") (pintype "unspecified"))
      (node (ref "U16") (pin "5") (pinfunction "VDD_5") (pintype "unspecified"))
      (node (ref "U6") (pin "2") (pinfunction "VOUT(TAB)_2") (pintype "unspecified"))
      (node (ref "U6") (pin "4") (pinfunction "TAB_4") (pintype "unspecified"))
      (node (ref "U9") (pin "1") (pinfunction "1_1") (pintype "input"))
    )
    (net (code "64") (name "BAT") (class "Default")
      (node (ref "C12") (pin "1") (pinfunction "1_1") (pintype "input"))
      (node (ref "CN1") (pin "2") (pinfunction "2_2") (pintype "unspecified"))
      (node (ref "SW2") (pin "2") (pinfunction "2_2") (pintype "unspecified"))
      (node (ref "U10") (pin "5") (pinfunction "BAT_5") (pintype "input"))
    )
    (net (code "65") (name "GND") (class "Default")
      (node (ref "C10") (pin "1") (pinfunction "1_1") (pintype "input"))
      (node (ref "C11") (pin "2") (pinfunction "2_2") (pintype "input"))
      (node (ref "C12") (pin "2") (pinfunction "2_2") (pintype "input"))
      (node (ref "C14") (pin "1") (pinfunction "1_1") (pintype "input"))
      (node (ref "C15") (pin "2") (pinfunction "2_2") (pintype "input"))
      (node (ref "C16") (pin "1") (pinfunction "1_1") (pintype "input"))
      (node (ref "C17") (pin "2") (pinfunction "2_2") (pintype "input"))
      (node (ref "C18") (pin "2") (pinfunction "2_2") (pintype "input"))
      (node (ref "C21") (pin "1") (pinfunction "1_1") (pintype "input"))
      (node (ref "C22") (pin "1") (pinfunction "1_1") (pintype "input"))
      (node (ref "C23") (pin "1") (pinfunction "1_1") (pintype "input"))
      (node (ref "C24") (pin "1") (pinfunction "1_1") (pintype "input"))
      (node (ref "C25") (pin "2") (pinfunction "2_2") (pintype "input"))
      (node (ref "C3") (pin "2") (pinfunction "2_2") (pintype "input"))
      (node (ref "C5") (pin "1") (pinfunction "1_1") (pintype "input"))
      (node (ref "C9") (pin "1") (pinfunction "1_1") (pintype "input"))
      (node (ref "CN1") (pin "1") (pinfunction "1_1") (pintype "unspecified"))
      (node (ref "H1") (pin "2") (pinfunction "2_2") (pintype "unspecified"))
      (node (ref "H2") (pin "1") (pinfunction "1_1") (pintype "unspecified"))
      (node (ref "H3") (pin "1") (pinfunction "1_1") (pintype "unspecified"))
      (node (ref "H5") (pin "1") (pinfunction "1_1") (pintype "unspecified"))
      (node (ref "H6") (pin "1") (pinfunction "1_1") (pintype "input"))
      (node (ref "H7") (pin "2") (pinfunction "2_2") (pintype "unspecified"))
      (node (ref "LED1") (pin "1") (pinfunction "C_1") (pintype "input"))
      (node (ref "LED5") (pin "1") (pinfunction "C_1") (pintype "input"))
      (node (ref "LED6") (pin "1") (pinfunction "C_1") (pintype "input"))
      (node (ref "LED7") (pin "1") (pinfunction "C_1") (pintype "input"))
      (node (ref "LED8") (pin "1") (pinfunction "C_1") (pintype "input"))
      (node (ref "R16") (pin "2") (pinfunction "2_2") (pintype "input"))
      (node (ref "R23") (pin "1") (pinfunction "1_1") (pintype "input"))
      (node (ref "R30") (pin "1") (pinfunction "1_1") (pintype "input"))
      (node (ref "R31") (pin "1") (pinfunction "1_1") (pintype "input"))
      (node (ref "R35") (pin "1") (pinfunction "1_1") (pintype "input"))
      (node (ref "R36") (pin "2") (pinfunction "2_2") (pintype "input"))
      (node (ref "R38") (pin "1") (pinfunction "1_1") (pintype "input"))
      (node (ref "R9") (pin "1") (pinfunction "1_1") (pintype "input"))
      (node (ref "SW4") (pin "2") (pinfunction "2_2") (pintype "unspecified"))
      (node (ref "SW5") (pin "2") (pinfunction "2_2") (pintype "unspecified"))
      (node (ref "SW6") (pin "2") (pinfunction "2_2") (pintype "unspecified"))
      (node (ref "SW7") (pin "2") (pinfunction "2_2") (pintype "unspecified"))
      (node (ref "U1") (pin "17") (pinfunction "Gnd/AGnd_17") (pintype "unspecified"))
      (node (ref "U10") (pin "1") (pinfunction "TEMP_1") (pintype "input"))
      (node (ref "U10") (pin "3") (pinfunction "GND_3") (pintype "input"))
      (node (ref "U10") (pin "9") (pinfunction "EP_9") (pintype "input"))
      (node (ref "U12") (pin "4") (pinfunction "GND_4") (pintype "unspecified"))
      (node (ref "U13") (pin "1") (pinfunction "CLKIN_1") (pintype "unspecified"))
      (node (ref "U13") (pin "11") (pinfunction "FSYNC_11") (pintype "unspecified"))
      (node (ref "U13") (pin "18") (pinfunction "GND_18") (pintype "unspecified"))
      (node (ref "U14") (pin "1") (pinfunction "1_1") (pintype "unspecified"))
      (node (ref "U16") (pin "2") (pinfunction "VSS_2") (pintype "unspecified"))
      (node (ref "U17") (pin "1") (pinfunction "1_1") (pintype "unspecified"))
      (node (ref "U18") (pin "25") (pinfunction "25_25") (pintype "unspecified"))
      (node (ref "U18") (pin "A1") (pinfunction "GND_A1") (pintype "unspecified"))
      (node (ref "U18") (pin "A12") (pinfunction "GND_A12") (pintype "unspecified"))
      (node (ref "U18") (pin "B1") (pinfunction "GND_B1") (pintype "unspecified"))
      (node (ref "U18") (pin "B12") (pinfunction "GND_B12") (pintype "unspecified"))
      (node (ref "U2") (pin "3") (pinfunction "GND_3") (pintype "unspecified"))
      (node (ref "U6") (pin "1") (pinfunction "ADJ(GND)_1") (pintype "unspecified"))
      (node (ref "U9") (pin "2") (pinfunction "2_2") (pintype "input"))
      (node (ref "USB2") (pin "0") (pinfunction "SH_0") (pintype "unspecified"))
      (node (ref "USB2") (pin "1") (pinfunction "SH_1") (pintype "unspecified"))
      (node (ref "USB2") (pin "2") (pinfunction "SH_2") (pintype "unspecified"))
      (node (ref "USB2") (pin "3") (pinfunction "SH_3") (pintype "unspecified"))
      (node (ref "USB2") (pin "A1") (pinfunction "GND_A1") (pintype "unspecified"))
      (node (ref "USB2") (pin "A12") (pinfunction "GND_A12") (pintype "unspecified"))
      (node (ref "USB2") (pin "B1") (pinfunction "GND_B1") (pintype "unspecified"))
      (node (ref "USB2") (pin "B12") (pinfunction "GND_B12") (pintype "unspecified"))
      (node (ref "USB3") (pin "25") (pinfunction "SHELL_25") (pintype "unspecified"))
      (node (ref "USB3") (pin "26") (pinfunction "SHELL_26") (pintype "unspecified"))
      (node (ref "USB3") (pin "A1") (pinfunction "GND_A1") (pintype "unspecified"))
      (node (ref "USB3") (pin "A12") (pinfunction "GND_A12") (pintype "unspecified"))
      (node (ref "USB3") (pin "B1") (pinfunction "GND_B1") (pintype "unspecified"))
      (node (ref "USB3") (pin "B12") (pinfunction "GND_B12") (pintype "unspecified"))
    )
    (net (code "66") (name "Net-(D1-A)") (class "Default")
      (node (ref "D1") (pin "2") (pinfunction "A_2") (pintype "unspecified"))
      (node (ref "U1") (pin "19") (pinfunction "P3.0/PWM30/RxD/INT4_19") (pintype "unspecified"))
    )
    (net (code "67") (name "Net-(LED1-A)") (class "Default")
      (node (ref "LED1") (pin "2") (pinfunction "A_2") (pintype "input"))
      (node (ref "R6") (pin "2") (pinfunction "2_2") (pintype "input"))
    )
    (net (code "68") (name "Net-(LED2-A)") (class "Default")
      (node (ref "LED2") (pin "2") (pinfunction "A_2") (pintype "input"))
      (node (ref "U10") (pin "7") (pinfunction "CHRG#_7") (pintype "input"))
    )
    (net (code "69") (name "Net-(LED2-C)") (class "Default")
      (node (ref "LED2") (pin "1") (pinfunction "C_1") (pintype "input"))
      (node (ref "R11") (pin "1") (pinfunction "1_1") (pintype "input"))
    )
    (net (code "70") (name "Net-(LED3-A)") (class "Default")
      (node (ref "LED3") (pin "2") (pinfunction "A_2") (pintype "input"))
      (node (ref "U10") (pin "6") (pinfunction "STDBY#_6") (pintype "input"))
    )
    (net (code "71") (name "Net-(LED3-C)") (class "Default")
      (node (ref "LED3") (pin "1") (pinfunction "C_1") (pintype "input"))
      (node (ref "R12") (pin "1") (pinfunction "1_1") (pintype "input"))
    )
    (net (code "72") (name "Net-(LED5-A)") (class "Default")
      (node (ref "LED5") (pin "2") (pinfunction "A_2") (pintype "input"))
      (node (ref "R15") (pin "1") (pinfunction "1_1") (pintype "input"))
    )
    (net (code "73") (name "Net-(LED6-A)") (class "Default")
      (node (ref "LED6") (pin "2") (pinfunction "A_2") (pintype "input"))
      (node (ref "R26") (pin "2") (pinfunction "2_2") (pintype "input"))
    )
    (net (code "74") (name "Net-(LED7-A)") (class "Default")
      (node (ref "LED7") (pin "2") (pinfunction "A_2") (pintype "input"))
      (node (ref "R27") (pin "2") (pinfunction "2_2") (pintype "input"))
    )
    (net (code "75") (name "Net-(LED8-A)") (class "Default")
      (node (ref "LED8") (pin "2") (pinfunction "A_2") (pintype "input"))
      (node (ref "R28") (pin "2") (pinfunction "2_2") (pintype "input"))
    )
    (net (code "76") (name "Net-(R33-Pad2)") (class "Default")
      (node (ref "R33") (pin "2") (pinfunction "2_2") (pintype "input"))
      (node (ref "SW7") (pin "1") (pinfunction "1_1") (pintype "unspecified"))
    )
    (net (code "77") (name "Net-(U2-V3)") (class "Default")
      (node (ref "C3") (pin "1") (pinfunction "1_1") (pintype "input"))
      (node (ref "U2") (pin "10") (pinfunction "V3_10") (pintype "unspecified"))
    )
    (net (code "78") (name "Net-(U2-VCC)") (class "Default")
      (node (ref "C4") (pin "2") (pinfunction "2_2") (pintype "input"))
      (node (ref "U2") (pin "7") (pinfunction "VCC_7") (pintype "unspecified"))
    )
    (net (code "79") (name "Net-(U10-CE)") (class "Default")
      (node (ref "R11") (pin "2") (pinfunction "2_2") (pintype "input"))
      (node (ref "R12") (pin "2") (pinfunction "2_2") (pintype "input"))
      (node (ref "R13") (pin "1") (pinfunction "1_1") (pintype "input"))
      (node (ref "U10") (pin "4") (pinfunction "VCC_4") (pintype "input"))
      (node (ref "U10") (pin "8") (pinfunction "CE_8") (pintype "input"))
    )
    (net (code "80") (name "Net-(U10-PROG)") (class "Default")
      (node (ref "R9") (pin "2") (pinfunction "2_2") (pintype "input"))
      (node (ref "U10") (pin "2") (pinfunction "PROG_2") (pintype "input"))
    )
    (net (code "81") (name "Net-(U13-AD0)") (class "Default")
      (node (ref "R16") (pin "1") (pinfunction "1_1") (pintype "input"))
      (node (ref "U13") (pin "9") (pinfunction "AD0_9") (pintype "unspecified"))
    )
    (net (code "82") (name "Net-(U13-CPOUT)") (class "Default")
      (node (ref "C17") (pin "1") (pinfunction "1_1") (pintype "input"))
      (node (ref "U13") (pin "20") (pinfunction "CPOUT_20") (pintype "unspecified"))
    )
    (net (code "83") (name "Net-(U13-REGOUT)") (class "Default")
      (node (ref "C16") (pin "2") (pinfunction "2_2") (pintype "input"))
      (node (ref "U13") (pin "10") (pinfunction "REGOUT_10") (pintype "unspecified"))
    )
    (net (code "84") (name "Net-(U13-VDD)") (class "Default")
      (node (ref "C18") (pin "1") (pinfunction "1_1") (pintype "input"))
      (node (ref "U13") (pin "13") (pinfunction "VDD_13") (pintype "unspecified"))
    )
    (net (code "85") (name "Net-(U16-IN+)") (class "Default")
      (node (ref "R23") (pin "2") (pinfunction "2_2") (pintype "input"))
      (node (ref "R24") (pin "1") (pinfunction "1_1") (pintype "input"))
      (node (ref "U16") (pin "1") (pinfunction "IN+_1") (pintype "unspecified"))
    )
    (net (code "86") (name "Net-(U16-IN-)") (class "Default")
      (node (ref "R20") (pin "2") (pinfunction "2_2") (pintype "input"))
      (node (ref "R21") (pin "1") (pinfunction "1_1") (pintype "input"))
      (node (ref "U16") (pin "3") (pinfunction "IN-_3") (pintype "unspecified"))
    )
    (net (code "87") (name "Net-(USB2-CC1)") (class "Default")
      (node (ref "R36") (pin "1") (pinfunction "1_1") (pintype "input"))
      (node (ref "USB2") (pin "A5") (pinfunction "CC1_A5") (pintype "unspecified"))
    )
    (net (code "88") (name "Net-(USB2-CC2)") (class "Default")
      (node (ref "R35") (pin "2") (pinfunction "2_2") (pintype "input"))
      (node (ref "USB2") (pin "B5") (pinfunction "CC2_B5") (pintype "unspecified"))
    )
    (net (code "89") (name "VBUS") (class "Default")
      (node (ref "C11") (pin "1") (pinfunction "1_1") (pintype "input"))
      (node (ref "C4") (pin "1") (pinfunction "1_1") (pintype "input"))
      (node (ref "R13") (pin "2") (pinfunction "2_2") (pintype "input"))
      (node (ref "USB2") (pin "A4") (pinfunction "VBUS_A4") (pintype "unspecified"))
      (node (ref "USB2") (pin "A9") (pinfunction "VBUS_A9") (pintype "unspecified"))
      (node (ref "USB2") (pin "B4") (pinfunction "VBUS_B4") (pintype "unspecified"))
      (node (ref "USB2") (pin "B9") (pinfunction "VBUS_B9") (pintype "unspecified"))
    )
    (net (code "90") (name "VCC") (class "Default")
      (node (ref "C10") (pin "2") (pinfunction "2_2") (pintype "input"))
      (node (ref "C9") (pin "2") (pinfunction "2_2") (pintype "input"))
      (node (ref "SW2") (pin "1") (pinfunction "1_1") (pintype "unspecified"))
      (node (ref "U6") (pin "3") (pinfunction "VIN_3") (pintype "unspecified"))
    )
    (net (code "91") (name "VIN") (class "Default")
      (node (ref "R21") (pin "2") (pinfunction "2_2") (pintype "input"))
      (node (ref "R22") (pin "2") (pinfunction "2_2") (pintype "unspecified"))
      (node (ref "R29") (pin "2") (pinfunction "2_2") (pintype "input"))
      (node (ref "USB3") (pin "A4") (pinfunction "VBUS_A4") (pintype "unspecified"))
      (node (ref "USB3") (pin "A9") (pinfunction "VBUS_A9") (pintype "unspecified"))
      (node (ref "USB3") (pin "B4") (pinfunction "VBUS_B4") (pintype "unspecified"))
      (node (ref "USB3") (pin "B9") (pinfunction "VBUS_B9") (pintype "unspecified"))
    )
    (net (code "92") (name "VOUT") (class "Default")
      (node (ref "R22") (pin "1") (pinfunction "1_1") (pintype "unspecified"))
      (node (ref "R24") (pin "2") (pinfunction "2_2") (pintype "input"))
      (node (ref "U18") (pin "A4") (pinfunction "VBUS_A4") (pintype "unspecified"))
      (node (ref "U18") (pin "A9") (pinfunction "VBUS_A9") (pintype "unspecified"))
      (node (ref "U18") (pin "B4") (pinfunction "VBUS_B4") (pintype "unspecified"))
      (node (ref "U18") (pin "B9") (pinfunction "VBUS_B9") (pintype "unspecified"))
    )
    (net (code "93") (name "V_WAV") (class "Default")
      (node (ref "C25") (pin "1") (pinfunction "1_1") (pintype "input"))
      (node (ref "H7") (pin "1") (pinfunction "1_1") (pintype "unspecified"))
      (node (ref "R37") (pin "2") (pinfunction "2_2") (pintype "input"))
    )
    (net (code "94") (name "unconnected-(H1-Pad4)") (class "Default")
      (node (ref "H1") (pin "4") (pinfunction "4_4") (pintype "unspecified+no_connect"))
    )
    (net (code "95") (name "unconnected-(H1-Pad6)") (class "Default")
      (node (ref "H1") (pin "6") (pinfunction "6_6") (pintype "unspecified+no_connect"))
    )
    (net (code "96") (name "unconnected-(SCREW1-Pad1)") (class "Default")
      (node (ref "SCREW1") (pin "1") (pinfunction "1_1") (pintype "input+no_connect"))
    )
    (net (code "97") (name "unconnected-(SCREW2-Pad1)") (class "Default")
      (node (ref "SCREW2") (pin "1") (pinfunction "1_1") (pintype "input+no_connect"))
    )
    (net (code "98") (name "unconnected-(SCREW3-Pad1)") (class "Default")
      (node (ref "SCREW3") (pin "1") (pinfunction "1_1") (pintype "input+no_connect"))
    )
    (net (code "99") (name "unconnected-(SCREW4-Pad1)") (class "Default")
      (node (ref "SCREW4") (pin "1") (pinfunction "1_1") (pintype "input+no_connect"))
    )
    (net (code "100") (name "unconnected-(SCREW5-Pad1)") (class "Default")
      (node (ref "SCREW5") (pin "1") (pinfunction "1_1") (pintype "input+no_connect"))
    )
    (net (code "101") (name "unconnected-(SCREW7-Pad1)") (class "Default")
      (node (ref "SCREW7") (pin "1") (pinfunction "1_1") (pintype "input+no_connect"))
    )
    (net (code "102") (name "unconnected-(SCREW8-Pad1)") (class "Default")
      (node (ref "SCREW8") (pin "1") (pinfunction "1_1") (pintype "input+no_connect"))
    )
    (net (code "103") (name "unconnected-(SCREW9-Pad1)") (class "Default")
      (node (ref "SCREW9") (pin "1") (pinfunction "1_1") (pintype "input+no_connect"))
    )
    (net (code "104") (name "unconnected-(SCREW10-Pad1)") (class "Default")
      (node (ref "SCREW10") (pin "1") (pinfunction "1_1") (pintype "input+no_connect"))
    )
    (net (code "105") (name "unconnected-(SCREW11-Pad1)") (class "Default")
      (node (ref "SCREW11") (pin "1") (pinfunction "1_1") (pintype "input+no_connect"))
    )
    (net (code "106") (name "unconnected-(SCREW12-Pad1)") (class "Default")
      (node (ref "SCREW12") (pin "1") (pinfunction "1_1") (pintype "input+no_connect"))
    )
    (net (code "107") (name "unconnected-(SW2-Pad3)") (class "Default")
      (node (ref "SW2") (pin "3") (pinfunction "3_3") (pintype "unspecified+no_connect"))
    )
    (net (code "108") (name "unconnected-(U2-CTS#-Pad5)") (class "Default")
      (node (ref "U2") (pin "5") (pinfunction "CTS#_5") (pintype "unspecified+no_connect"))
    )
    (net (code "109") (name "unconnected-(U2-RTS#-Pad4)") (class "Default")
      (node (ref "U2") (pin "4") (pinfunction "RTS#_4") (pintype "unspecified+no_connect"))
    )
    (net (code "110") (name "unconnected-(U13-AUX_CL-Pad7)") (class "Default")
      (node (ref "U13") (pin "7") (pinfunction "AUX_CL_7") (pintype "unspecified+no_connect"))
    )
    (net (code "111") (name "unconnected-(U13-AUX_DA-Pad6)") (class "Default")
      (node (ref "U13") (pin "6") (pinfunction "AUX_DA_6") (pintype "unspecified+no_connect"))
    )
    (net (code "112") (name "unconnected-(U13-EP-Pad25)") (class "Default")
      (node (ref "U13") (pin "25") (pinfunction "EP_25") (pintype "unspecified+no_connect"))
    )
    (net (code "113") (name "unconnected-(U13-NC-Pad2)") (class "Default")
      (node (ref "U13") (pin "2") (pinfunction "NC_2") (pintype "unspecified+no_connect"))
    )
    (net (code "114") (name "unconnected-(U13-NC-Pad3)") (class "Default")
      (node (ref "U13") (pin "3") (pinfunction "NC_3") (pintype "unspecified+no_connect"))
    )
    (net (code "115") (name "unconnected-(U13-NC-Pad4)") (class "Default")
      (node (ref "U13") (pin "4") (pinfunction "NC_4") (pintype "unspecified+no_connect"))
    )
    (net (code "116") (name "unconnected-(U13-NC-Pad5)") (class "Default")
      (node (ref "U13") (pin "5") (pinfunction "NC_5") (pintype "unspecified+no_connect"))
    )
    (net (code "117") (name "unconnected-(U13-NC-Pad14)") (class "Default")
      (node (ref "U13") (pin "14") (pinfunction "NC_14") (pintype "unspecified+no_connect"))
    )
    (net (code "118") (name "unconnected-(U13-NC-Pad15)") (class "Default")
      (node (ref "U13") (pin "15") (pinfunction "NC_15") (pintype "unspecified+no_connect"))
    )
    (net (code "119") (name "unconnected-(U13-NC-Pad16)") (class "Default")
      (node (ref "U13") (pin "16") (pinfunction "NC_16") (pintype "unspecified+no_connect"))
    )
    (net (code "120") (name "unconnected-(U13-NC-Pad17)") (class "Default")
      (node (ref "U13") (pin "17") (pinfunction "NC_17") (pintype "unspecified+no_connect"))
    )
    (net (code "121") (name "unconnected-(U13-RESV-Pad19)") (class "Default")
      (node (ref "U13") (pin "19") (pinfunction "RESV_19") (pintype "unspecified+no_connect"))
    )
    (net (code "122") (name "unconnected-(U13-RESV-Pad21)") (class "Default")
      (node (ref "U13") (pin "21") (pinfunction "RESV_21") (pintype "unspecified+no_connect"))
    )
    (net (code "123") (name "unconnected-(U13-RESV-Pad22)") (class "Default")
      (node (ref "U13") (pin "22") (pinfunction "RESV_22") (pintype "unspecified+no_connect"))
    )
    (net (code "124") (name "unconnected-(U14-Pad2)") (class "Default")
      (node (ref "U14") (pin "2") (pinfunction "2_2") (pintype "unspecified+no_connect"))
    )
    (net (code "125") (name "unconnected-(U14-Pad5)") (class "Default")
      (node (ref "U14") (pin "5") (pinfunction "5_5") (pintype "unspecified+no_connect"))
    )
    (net (code "126") (name "unconnected-(U14-Pad6)") (class "Default")
      (node (ref "U14") (pin "6") (pinfunction "6_6") (pintype "unspecified+no_connect"))
    )
    (net (code "127") (name "unconnected-(U17-Pad2)") (class "Default")
      (node (ref "U17") (pin "2") (pinfunction "2_2") (pintype "unspecified+no_connect"))
    )
    (net (code "128") (name "unconnected-(U17-Pad5)") (class "Default")
      (node (ref "U17") (pin "5") (pinfunction "5_5") (pintype "unspecified+no_connect"))
    )
    (net (code "129") (name "unconnected-(U17-Pad6)") (class "Default")
      (node (ref "U17") (pin "6") (pinfunction "6_6") (pintype "unspecified+no_connect"))
    )
    (net (code "130") (name "unconnected-(USB2-SBU1-PadA8)") (class "Default")
      (node (ref "USB2") (pin "A8") (pinfunction "SBU1_A8") (pintype "unspecified+no_connect"))
    )
    (net (code "131") (name "unconnected-(USB2-SBU2-PadB8)") (class "Default")
      (node (ref "USB2") (pin "B8") (pinfunction "SBU2_B8") (pintype "unspecified+no_connect"))
    )
  )
)
